# DCDC3.net
KiCad netlist of a schematic drawn in Altium Designer
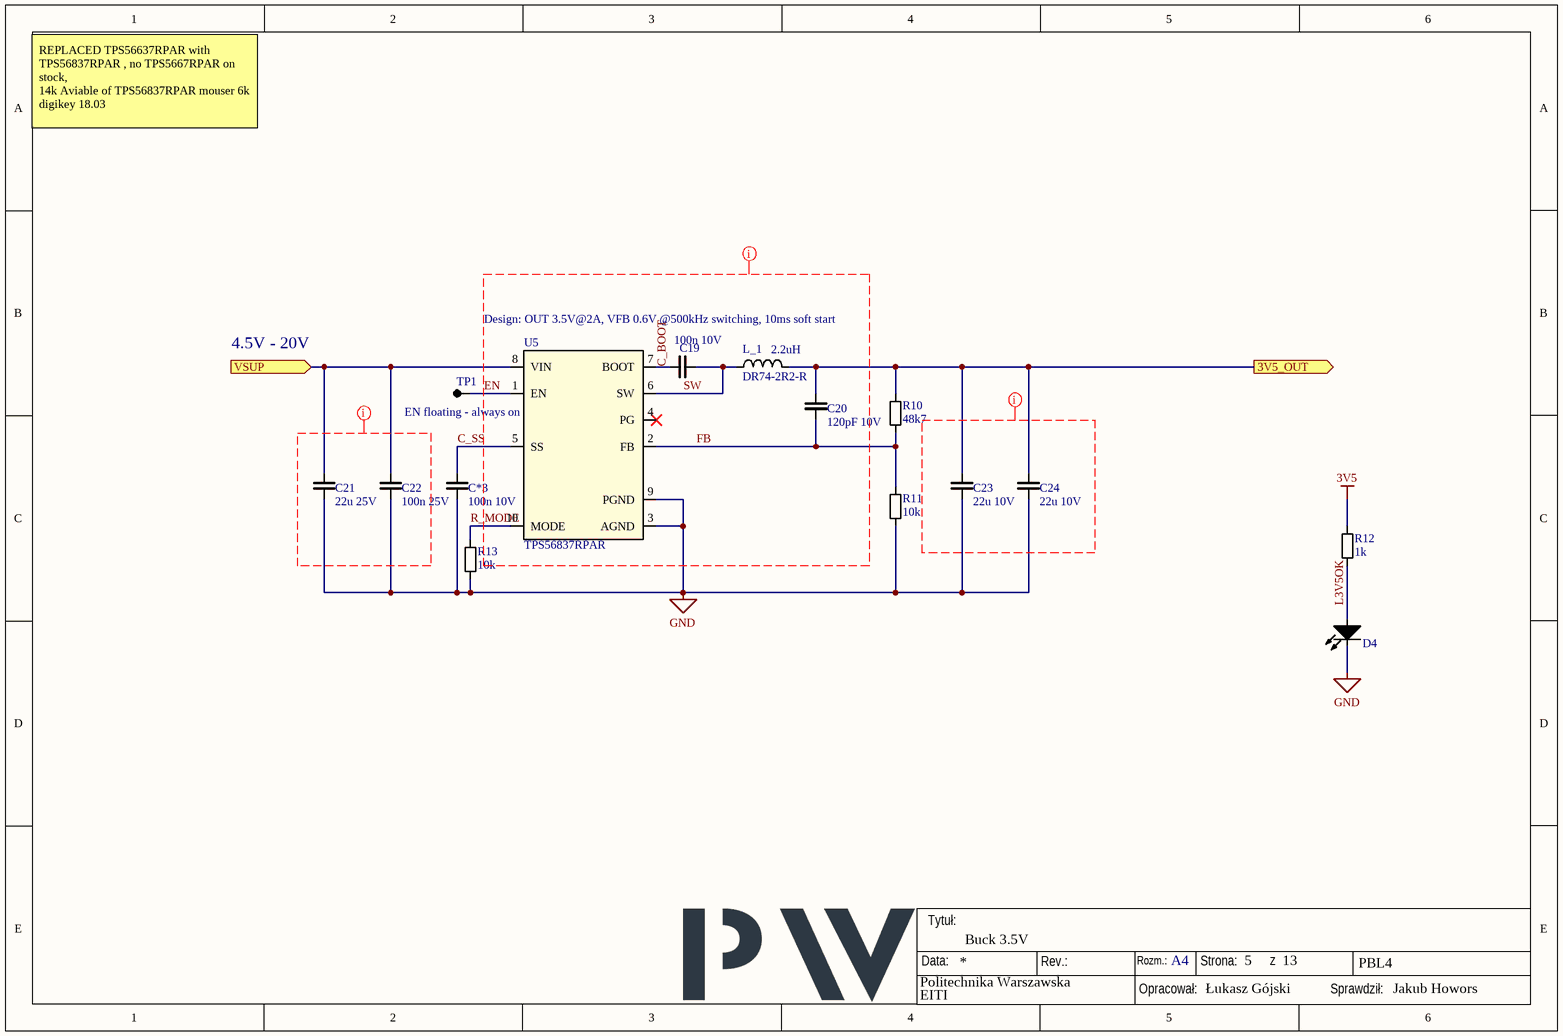
[diagram p0: DCDC3.SchDoc]

(export (version "E")
  (design (tool "Eeschema 10.0.6"))
  (components
    (comp (ref "C*3")
      (value "100n 10V")
      (footprint "C_0603")
      (description "Ceramic capacitor")
      (fields (field (name "VOLTAGE") "10V") (field (name "TOLERANCE") "10%"))
      (libsource (lib "") (part "C_100nF_10V_1"))
    )
    (comp (ref "C19")
      (value "100n 10V")
      (footprint "C_0603")
      (description "Ceramic capacitor")
      (fields (field (name "VOLTAGE") "10V") (field (name "TOLERANCE") "10%"))
      (libsource (lib "Common") (part "C_100nF_10V"))
    )
    (comp (ref "C20")
      (value "120pF 10V")
      (footprint "C_0603")
      (description "Ceramic capacitor")
      (fields (field (name "VOLTAGE") "10V") (field (name "TOLERANCE") "10%"))
      (libsource (lib "Common") (part "C_120pF_10V"))
    )
    (comp (ref "C21")
      (value "22u 25V")
      (footprint "C_1206")
      (description "Ceramic capacitor")
      (fields (field (name "VOLTAGE") "25V") (field (name "TOLERANCE") "20%"))
      (libsource (lib "Common") (part "C_22uF_25V"))
    )
    (comp (ref "C22")
      (value "100n 25V")
      (footprint "C_0603")
      (description "Ceramic capacitor")
      (fields (field (name "VOLTAGE") "25V") (field (name "TOLERANCE") "10%"))
      (libsource (lib "Common") (part "C_100nF_25V"))
    )
    (comp (ref "C23")
      (value "22u 10V")
      (footprint "C_1206")
      (description "Ceramic capacitor")
      (fields (field (name "VOLTAGE") "10V") (field (name "TOLERANCE") "20%"))
      (libsource (lib "Common") (part "C_22uF_10V"))
    )
    (comp (ref "C24")
      (value "22u 10V")
      (footprint "C_1206")
      (description "Ceramic capacitor")
      (fields (field (name "VOLTAGE") "10V") (field (name "TOLERANCE") "20%"))
      (libsource (lib "Common") (part "C_22uF_10V"))
    )
    (comp (ref "D4")
      (value "RED")
      (footprint "LED_0603")
      (description "LED RED 0603 3.3V")
      (libsource (lib "Common") (part "LED_0603"))
    )
    (comp (ref "L_1")
      (value "DR74-2R2-R")
      (footprint "DR74-2R2-R")
      (description "Inductor, 2.2uF 4.76A")
      (fields (field (name "TOLERANCE") "20%") (field (name "MANUFACTURER") "EATON ELECTRONICS"))
      (libsource (lib "PowerLib") (part "L_2u2_4.76A_1"))
    )
    (comp (ref "R10")
      (value "48k7")
      (footprint "R_0603")
      (description "Resistor")
      (fields (field (name "TOLERANCE") "1%") (field (name "POWER") "100mW"))
      (libsource (lib "Common") (part "R_48k7"))
    )
    (comp (ref "R11")
      (value "10k")
      (footprint "R_0603")
      (description "Resistor")
      (fields (field (name "TOLERANCE") "1%") (field (name "POWER") "100mW"))
      (libsource (lib "Common") (part "R_10k"))
    )
    (comp (ref "R12")
      (value "1k")
      (footprint "R_0603")
      (description "Resistor")
      (fields (field (name "TOLERANCE") "1%") (field (name "POWER") "100mW"))
      (libsource (lib "Common") (part "R_1k"))
    )
    (comp (ref "R13")
      (value "10k")
      (footprint "R_0603")
      (description "Resistor")
      (fields (field (name "TOLERANCE") "1%") (field (name "POWER") "100mW"))
      (libsource (lib "Common") (part "R_10k"))
    )
    (comp (ref "TP1") (value "TP") (footprint "TP") (libsource (lib "Common") (part "TP")))
    (comp (ref "U5")
      (value "TPS56837RPAR")
      (footprint "RPA0010A-MFG")
      (description "Switching Voltage Regulators 4.5-V to 28-V input 8-A synchronous buck")
      (fields (field (name "MANUFACTURER") "Texas Instruments"))
      (libsource (lib "PowerLib") (part "TPS56837RPAR"))
    )
  )
  (nets
    (net (code "1") (name "/3V5_OUT") (class "Default")
      (node (ref "C20") (pin "2") (pinfunction "2_2") (pintype "passive"))
      (node (ref "C23") (pin "2") (pinfunction "2_2") (pintype "passive"))
      (node (ref "C24") (pin "2") (pinfunction "2_2") (pintype "passive"))
      (node (ref "L_1") (pin "2") (pinfunction "2_2") (pintype "passive"))
      (node (ref "R10") (pin "2") (pinfunction "2_2") (pintype "passive"))
    )
    (net (code "2") (name "/C_BOOT") (class "Default")
      (node (ref "C19") (pin "2") (pinfunction "2_2") (pintype "passive"))
      (node (ref "U5") (pin "7") (pinfunction "BOOT_7") (pintype "power_in"))
    )
    (net (code "3") (name "/C_SS") (class "Default")
      (node (ref "C*3") (pin "2") (pinfunction "2_2") (pintype "passive"))
      (node (ref "U5") (pin "5") (pinfunction "SS_5") (pintype "passive"))
    )
    (net (code "4") (name "/EN") (class "Default")
      (node (ref "TP1") (pin "1") (pinfunction "TP_1") (pintype "passive"))
      (node (ref "U5") (pin "1") (pinfunction "EN_1") (pintype "power_in"))
    )
    (net (code "5") (name "/FB") (class "Default")
      (node (ref "C20") (pin "1") (pinfunction "1_1") (pintype "passive"))
      (node (ref "R10") (pin "1") (pinfunction "1_1") (pintype "passive"))
      (node (ref "R11") (pin "2") (pinfunction "2_2") (pintype "passive"))
      (node (ref "U5") (pin "2") (pinfunction "FB_2") (pintype "power_in"))
    )
    (net (code "6") (name "/L3V5OK") (class "Default")
      (node (ref "D4") (pin "A") (pinfunction "A_A") (pintype "passive"))
      (node (ref "R12") (pin "1") (pinfunction "1_1") (pintype "passive"))
    )
    (net (code "7") (name "/R_MODE") (class "Default")
      (node (ref "R13") (pin "2") (pinfunction "2_2") (pintype "passive"))
      (node (ref "U5") (pin "10") (pinfunction "MODE_10") (pintype "power_in"))
    )
    (net (code "8") (name "/SW") (class "Default")
      (node (ref "C19") (pin "1") (pinfunction "1_1") (pintype "passive"))
      (node (ref "L_1") (pin "1") (pinfunction "1_1") (pintype "passive"))
      (node (ref "U5") (pin "6") (pinfunction "SW_6") (pintype "power_in"))
    )
    (net (code "9") (name "/VSUP") (class "Default")
      (node (ref "C21") (pin "2") (pinfunction "2_2") (pintype "passive"))
      (node (ref "C22") (pin "2") (pinfunction "2_2") (pintype "passive"))
      (node (ref "U5") (pin "8") (pinfunction "VIN_8") (pintype "passive"))
    )
    (net (code "10") (name "3V5") (class "Default")
      (node (ref "R12") (pin "2") (pinfunction "2_2") (pintype "passive"))
    )
    (net (code "11") (name "GND") (class "Default")
      (node (ref "C*3") (pin "1") (pinfunction "1_1") (pintype "passive"))
      (node (ref "C21") (pin "1") (pinfunction "1_1") (pintype "passive"))
      (node (ref "C22") (pin "1") (pinfunction "1_1") (pintype "passive"))
      (node (ref "C23") (pin "1") (pinfunction "1_1") (pintype "passive"))
      (node (ref "C24") (pin "1") (pinfunction "1_1") (pintype "passive"))
      (node (ref "D4") (pin "K") (pinfunction "K_K") (pintype "passive"))
      (node (ref "R11") (pin "1") (pinfunction "1_1") (pintype "passive"))
      (node (ref "R13") (pin "1") (pinfunction "1_1") (pintype "passive"))
      (node (ref "U5") (pin "3") (pinfunction "AGND_3") (pintype "power_in"))
      (node (ref "U5") (pin "9") (pinfunction "PGND_9") (pintype "power_in"))
    )
    (net (code "12") (name "unconnected-(U5-PG-Pad4)") (class "Default")
      (node (ref "U5") (pin "4") (pinfunction "PG_4") (pintype "power_in+no_connect"))
    )
  )
)
